# Core.net
KiCad netlist of a schematic drawn in Altium Designer
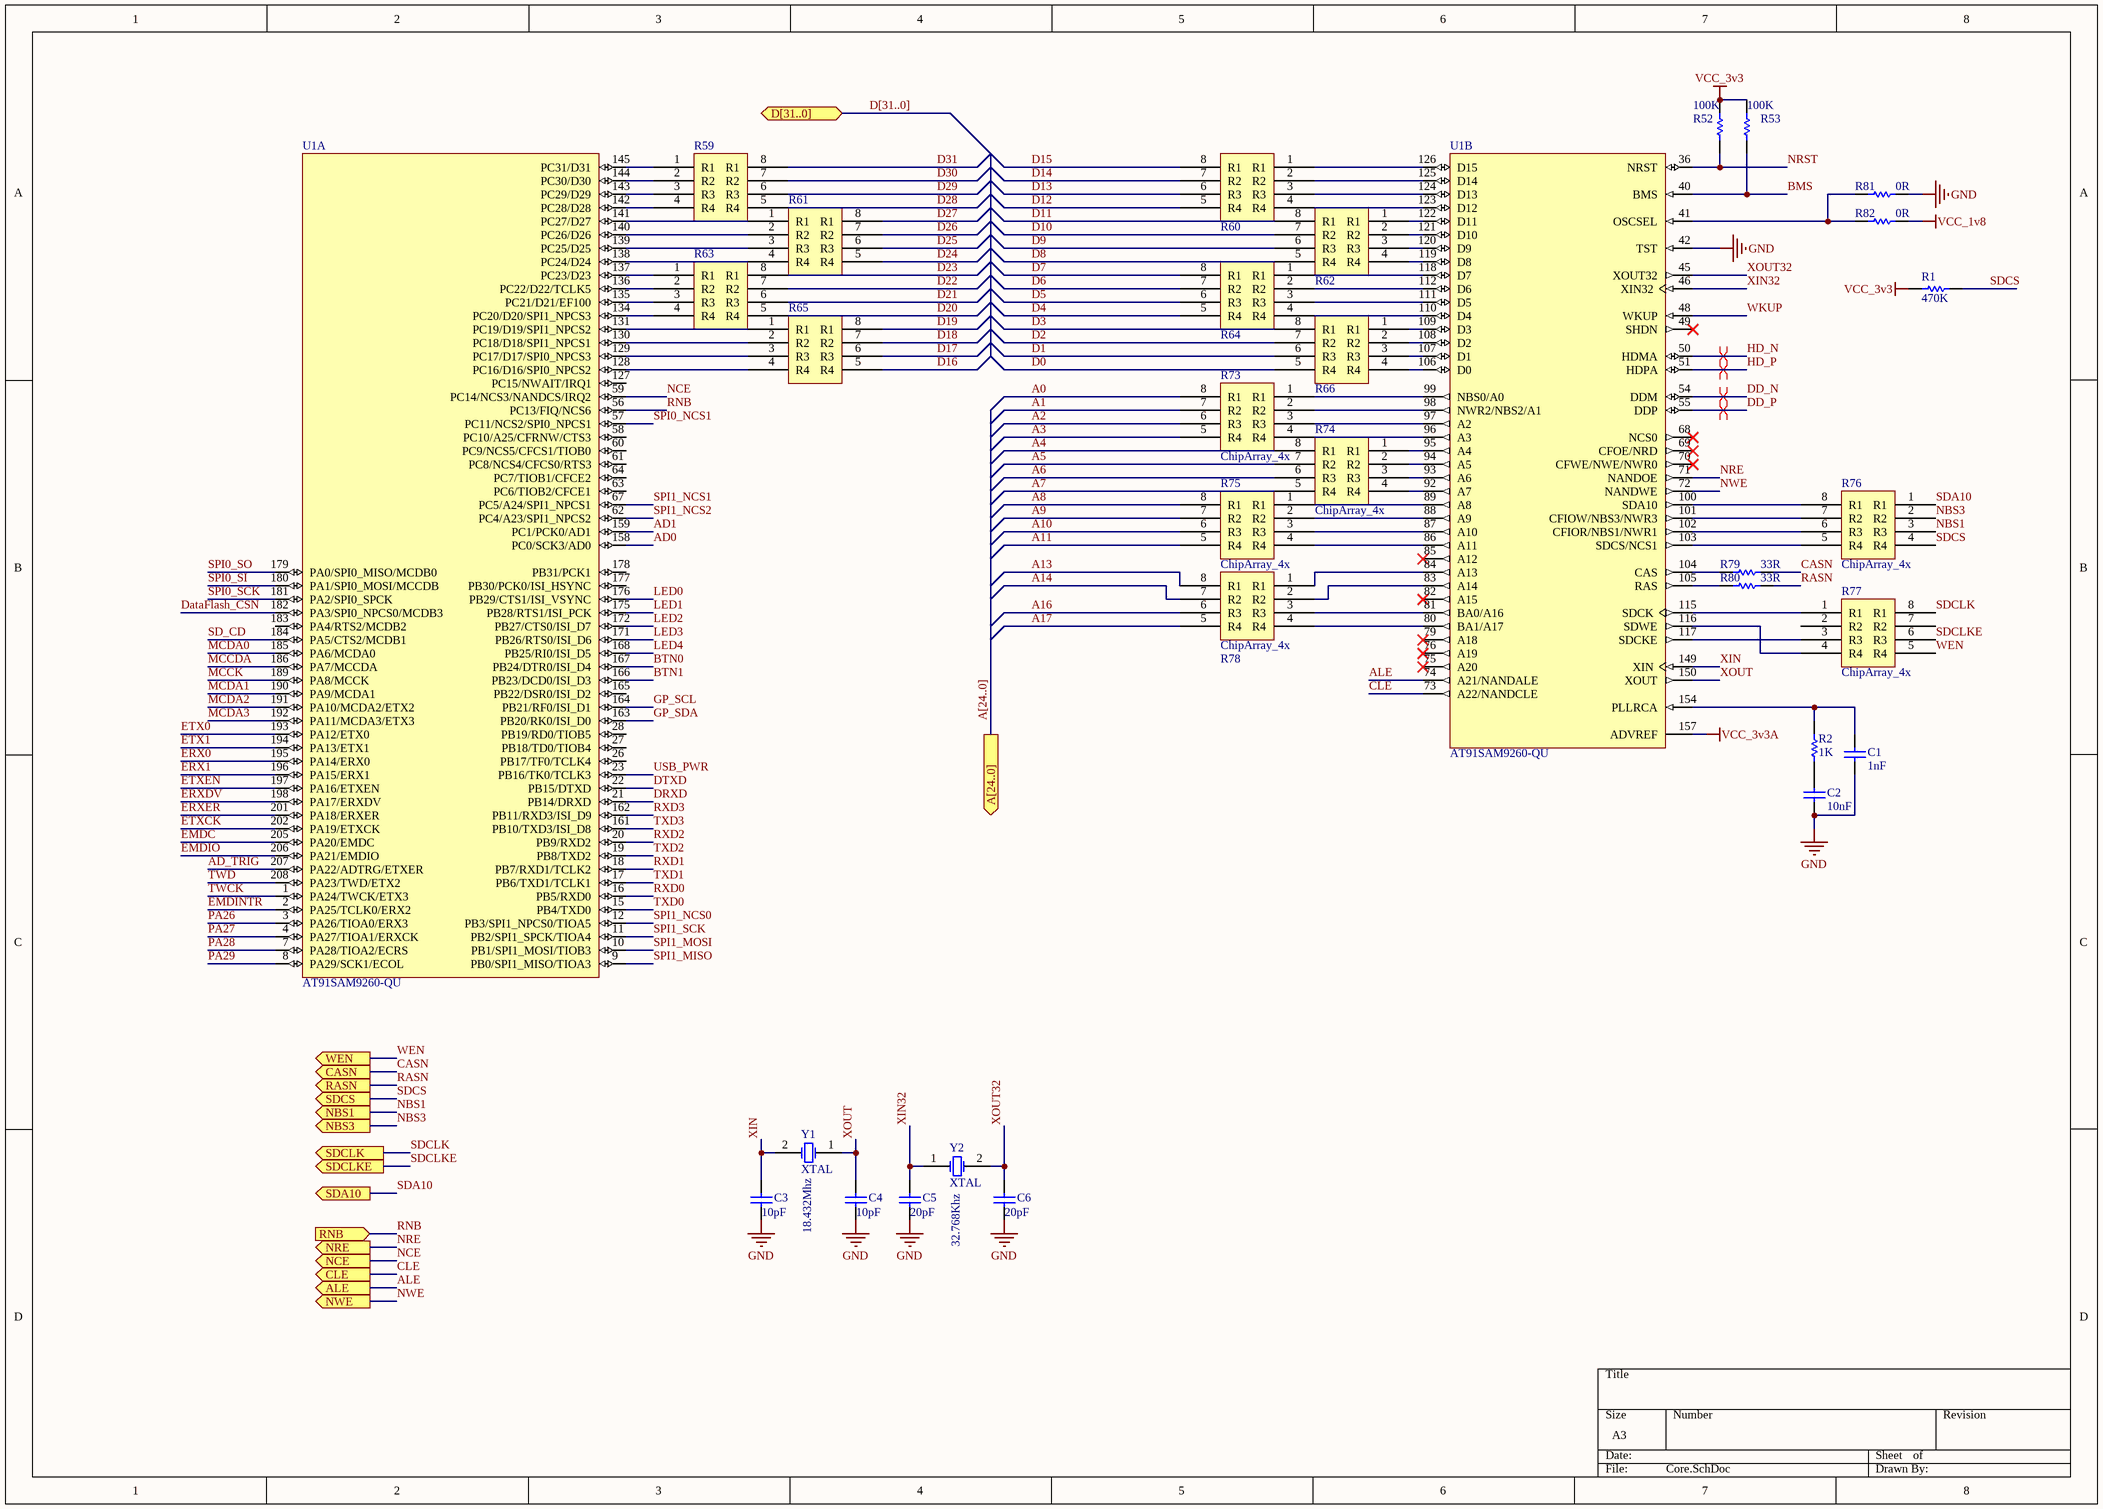
[diagram p0: Core.SchDoc]

(export (version "E")
  (design (tool "Eeschema 10.0.6"))
  (components
    (comp (ref "C1")
      (value "1nF")
      (footprint "C0805")
      (description "Capacitor")
      (fields (field (name "Comment") "Cap") (field (name "PUBLISHER") "Altium Limited"))
      (libsource (lib "Miscellaneous Devices") (part "Cap"))
    )
    (comp (ref "C2")
      (value "10nF")
      (footprint "C0805")
      (description "Capacitor")
      (fields (field (name "Comment") "Cap") (field (name "PUBLISHER") "Altium Limited"))
      (libsource (lib "Miscellaneous Devices") (part "Cap"))
    )
    (comp (ref "C3")
      (value "10pF")
      (footprint "C0805")
      (description "Capacitor")
      (fields (field (name "Comment") "Cap") (field (name "PUBLISHER") "Altium Limited"))
      (libsource (lib "Miscellaneous Devices") (part "Cap"))
    )
    (comp (ref "C4")
      (value "10pF")
      (footprint "C0805")
      (description "Capacitor")
      (fields (field (name "Comment") "Cap") (field (name "PUBLISHER") "Altium Limited"))
      (libsource (lib "Miscellaneous Devices") (part "Cap"))
    )
    (comp (ref "C5")
      (value "20pF")
      (footprint "0603PKG")
      (description "Capacitor")
      (fields (field (name "Comment") "Cap") (field (name "PUBLISHER") "Altium Limited"))
      (libsource (lib "Miscellaneous Devices") (part "Cap"))
    )
    (comp (ref "C6")
      (value "20pF")
      (footprint "0603PKG")
      (description "Capacitor")
      (fields (field (name "Comment") "Cap") (field (name "PUBLISHER") "Altium Limited"))
      (libsource (lib "Miscellaneous Devices") (part "Cap"))
    )
    (comp (ref "R1")
      (value "470K")
      (footprint "C0805")
      (description "Semiconductor Resistor")
      (fields (field (name "Comment") "Res Semi") (field (name "PUBLISHER") "Altium Limited"))
      (libsource (lib "Miscellaneous Devices") (part "Res Semi"))
    )
    (comp (ref "R2")
      (value "1K")
      (footprint "C0805")
      (description "Semiconductor Resistor")
      (fields (field (name "Comment") "Res Semi") (field (name "PUBLISHER") "Altium Limited"))
      (libsource (lib "Miscellaneous Devices") (part "Res Semi"))
    )
    (comp (ref "R52")
      (value "100K")
      (footprint "C0805")
      (description "Resistor")
      (fields (field (name "Comment") "Res1") (field (name "PUBLISHER") "Altium Limited"))
      (libsource (lib "Miscellaneous Devices") (part "Res1"))
    )
    (comp (ref "R53")
      (value "100K")
      (footprint "C0805")
      (description "Resistor")
      (fields (field (name "Comment") "Res1") (field (name "PUBLISHER") "Altium Limited"))
      (libsource (lib "Miscellaneous Devices") (part "Res1"))
    )
    (comp (ref "R59")
      (value "ChipArray_4x")
      (footprint "CAC-50P205X105-8M")
      (libsource (lib "") (part "ChipArray_4x_1"))
    )
    (comp (ref "R60")
      (value "ChipArray_4x")
      (footprint "CAC-50P205X105-8M")
      (libsource (lib "Connector_IntLib") (part "ChipArray_4x"))
    )
    (comp (ref "R61")
      (value "ChipArray_4x")
      (footprint "CAC-50P205X105-8M")
      (libsource (lib "") (part "ChipArray_4x_1"))
    )
    (comp (ref "R62")
      (value "ChipArray_4x")
      (footprint "CAC-50P205X105-8M")
      (libsource (lib "Connector_IntLib") (part "ChipArray_4x"))
    )
    (comp (ref "R63")
      (value "ChipArray_4x")
      (footprint "CAC-50P205X105-8M")
      (libsource (lib "") (part "ChipArray_4x_1"))
    )
    (comp (ref "R64")
      (value "ChipArray_4x")
      (footprint "CAC-50P205X105-8M")
      (libsource (lib "Connector_IntLib") (part "ChipArray_4x"))
    )
    (comp (ref "R65")
      (value "ChipArray_4x")
      (footprint "CAC-50P205X105-8M")
      (libsource (lib "") (part "ChipArray_4x_1"))
    )
    (comp (ref "R66")
      (value "ChipArray_4x")
      (footprint "CAC-50P205X105-8M")
      (libsource (lib "Connector_IntLib") (part "ChipArray_4x"))
    )
    (comp (ref "R73")
      (value "ChipArray_4x")
      (footprint "CAC-50P205X105-8M")
      (libsource (lib "Connector_IntLib") (part "ChipArray_4x"))
    )
    (comp (ref "R74")
      (value "ChipArray_4x")
      (footprint "CAC-50P205X105-8M")
      (libsource (lib "Connector_IntLib") (part "ChipArray_4x"))
    )
    (comp (ref "R75")
      (value "ChipArray_4x")
      (footprint "CAC-50P205X105-8M")
      (libsource (lib "Connector_IntLib") (part "ChipArray_4x"))
    )
    (comp (ref "R76")
      (value "ChipArray_4x")
      (footprint "CAC-50P205X105-8M")
      (libsource (lib "Connector_IntLib") (part "ChipArray_4x"))
    )
    (comp (ref "R77")
      (value "ChipArray_4x")
      (footprint "CAC-50P205X105-8M")
      (libsource (lib "") (part "ChipArray_4x_1"))
    )
    (comp (ref "R78")
      (value "ChipArray_4x")
      (footprint "CAC-50P205X105-8M")
      (libsource (lib "Connector_IntLib") (part "ChipArray_4x"))
    )
    (comp (ref "R79")
      (value "33R")
      (footprint "C0805")
      (description "Semiconductor Resistor")
      (fields (field (name "Comment") "Res Semi") (field (name "PUBLISHER") "Altium Limited"))
      (libsource (lib "Miscellaneous Devices") (part "Res Semi"))
    )
    (comp (ref "R80")
      (value "33R")
      (footprint "C0805")
      (description "Semiconductor Resistor")
      (fields (field (name "Comment") "Res Semi") (field (name "PUBLISHER") "Altium Limited"))
      (libsource (lib "Miscellaneous Devices") (part "Res Semi"))
    )
    (comp (ref "R81")
      (value "0R")
      (footprint "0603PKG")
      (description "Semiconductor Resistor")
      (fields (field (name "Comment") "Res Semi") (field (name "PUBLISHER") "Altium Limited"))
      (libsource (lib "Miscellaneous Devices") (part "Res Semi"))
    )
    (comp (ref "R82")
      (value "0R")
      (footprint "0603PKG")
      (description "Semiconductor Resistor")
      (fields (field (name "Comment") "Res Semi") (field (name "PUBLISHER") "Altium Limited"))
      (libsource (lib "Miscellaneous Devices") (part "Res Semi"))
    )
    (comp (ref "U1")
      (value "AT91SAM9260-QU")
      (footprint "SQFP50P3122X3122X245-208N")
      (libsource (lib "") (part "AT91SAM9260-QU_1"))
    )
    (comp (ref "Y1")
      (value "XTAL")
      (footprint "SMD_Crystal")
      (description "Crystal Oscillator")
      (fields (field (name "ALTIUM_VALUE") "18.432Mhz") (field (name "PUBLISHER") "Altium Limited"))
      (libsource (lib "Miscellaneous Devices") (part "XTAL"))
    )
    (comp (ref "Y2")
      (value "XTAL")
      (footprint "R38")
      (description "Crystal Oscillator")
      (fields (field (name "ALTIUM_VALUE") "32.768Khz") (field (name "PUBLISHER") "Altium Limited"))
      (libsource (lib "Miscellaneous Devices") (part "XTAL"))
    )
  )
  (nets
    (net (code "10") (name "/A0") (class "Default")
      (node (ref "R73") (pin "8") (pinfunction "R1_8") (pintype "passive"))
    )
    (net (code "11") (name "/A1") (class "Default")
      (node (ref "R73") (pin "7") (pinfunction "R2_7") (pintype "passive"))
    )
    (net (code "12") (name "/A2") (class "Default")
      (node (ref "R73") (pin "6") (pinfunction "R3_6") (pintype "passive"))
    )
    (net (code "13") (name "/A3") (class "Default")
      (node (ref "R73") (pin "5") (pinfunction "R4_5") (pintype "passive"))
    )
    (net (code "14") (name "/A4") (class "Default")
      (node (ref "R74") (pin "8") (pinfunction "R1_8") (pintype "passive"))
    )
    (net (code "15") (name "/A5") (class "Default")
      (node (ref "R74") (pin "7") (pinfunction "R2_7") (pintype "passive"))
    )
    (net (code "16") (name "/A6") (class "Default")
      (node (ref "R74") (pin "6") (pinfunction "R3_6") (pintype "passive"))
    )
    (net (code "17") (name "/A7") (class "Default")
      (node (ref "R74") (pin "5") (pinfunction "R4_5") (pintype "passive"))
    )
    (net (code "18") (name "/A8") (class "Default")
      (node (ref "R75") (pin "8") (pinfunction "R1_8") (pintype "passive"))
    )
    (net (code "19") (name "/A9") (class "Default")
      (node (ref "R75") (pin "7") (pinfunction "R2_7") (pintype "passive"))
    )
    (net (code "20") (name "/A10") (class "Default")
      (node (ref "R75") (pin "6") (pinfunction "R3_6") (pintype "passive"))
    )
    (net (code "21") (name "/A11") (class "Default")
      (node (ref "R75") (pin "5") (pinfunction "R4_5") (pintype "passive"))
    )
    (net (code "22") (name "/A13") (class "Default")
      (node (ref "R78") (pin "8") (pinfunction "R1_8") (pintype "passive"))
    )
    (net (code "23") (name "/A14") (class "Default")
      (node (ref "R78") (pin "7") (pinfunction "R2_7") (pintype "passive"))
    )
    (net (code "24") (name "/A16") (class "Default")
      (node (ref "R78") (pin "6") (pinfunction "R3_6") (pintype "passive"))
    )
    (net (code "25") (name "/A17") (class "Default")
      (node (ref "R78") (pin "5") (pinfunction "R4_5") (pintype "passive"))
    )
    (net (code "26") (name "/AD0") (class "Default")
      (node (ref "U1") (pin "158") (pinfunction "PC0/SCK3/AD0_158") (pintype "bidirectional"))
    )
    (net (code "27") (name "/AD1") (class "Default")
      (node (ref "U1") (pin "159") (pinfunction "PC1/PCK0/AD1_159") (pintype "bidirectional"))
    )
    (net (code "28") (name "/AD_TRIG") (class "Default")
      (node (ref "U1") (pin "207") (pinfunction "PA22/ADTRG/ETXER_207") (pintype "bidirectional"))
    )
    (net (code "29") (name "/ALE") (class "Default")
      (node (ref "U1") (pin "74") (pinfunction "A21/NANDALE_74") (pintype "output"))
    )
    (net (code "31") (name "/BMS") (class "Default")
      (node (ref "R53") (pin "1") (pinfunction "1_1") (pintype "passive"))
      (node (ref "U1") (pin "40") (pinfunction "BMS_40") (pintype "input"))
    )
    (net (code "32") (name "/BTN0") (class "Default")
      (node (ref "U1") (pin "167") (pinfunction "PB24/DTR0/ISI_D4_167") (pintype "bidirectional"))
    )
    (net (code "33") (name "/BTN1") (class "Default")
      (node (ref "U1") (pin "166") (pinfunction "PB23/DCD0/ISI_D3_166") (pintype "bidirectional"))
    )
    (net (code "34") (name "/CASN") (class "Default")
      (node (ref "R79") (pin "2") (pinfunction "2_2") (pintype "passive"))
    )
    (net (code "35") (name "/CLE") (class "Default")
      (node (ref "U1") (pin "73") (pinfunction "A22/NANDCLE_73") (pintype "output"))
    )
    (net (code "36") (name "/D0") (class "Default")
      (node (ref "R66") (pin "5") (pinfunction "R4_5") (pintype "passive"))
    )
    (net (code "37") (name "/D1") (class "Default")
      (node (ref "R66") (pin "6") (pinfunction "R3_6") (pintype "passive"))
    )
    (net (code "38") (name "/D2") (class "Default")
      (node (ref "R66") (pin "7") (pinfunction "R2_7") (pintype "passive"))
    )
    (net (code "39") (name "/D3") (class "Default")
      (node (ref "R66") (pin "8") (pinfunction "R1_8") (pintype "passive"))
    )
    (net (code "40") (name "/D4") (class "Default")
      (node (ref "R64") (pin "5") (pinfunction "R4_5") (pintype "passive"))
    )
    (net (code "41") (name "/D5") (class "Default")
      (node (ref "R64") (pin "6") (pinfunction "R3_6") (pintype "passive"))
    )
    (net (code "42") (name "/D6") (class "Default")
      (node (ref "R64") (pin "7") (pinfunction "R2_7") (pintype "passive"))
    )
    (net (code "43") (name "/D7") (class "Default")
      (node (ref "R64") (pin "8") (pinfunction "R1_8") (pintype "passive"))
    )
    (net (code "44") (name "/D8") (class "Default")
      (node (ref "R62") (pin "5") (pinfunction "R4_5") (pintype "passive"))
    )
    (net (code "45") (name "/D9") (class "Default")
      (node (ref "R62") (pin "6") (pinfunction "R3_6") (pintype "passive"))
    )
    (net (code "46") (name "/D10") (class "Default")
      (node (ref "R62") (pin "7") (pinfunction "R2_7") (pintype "passive"))
    )
    (net (code "47") (name "/D11") (class "Default")
      (node (ref "R62") (pin "8") (pinfunction "R1_8") (pintype "passive"))
    )
    (net (code "48") (name "/D12") (class "Default")
      (node (ref "R60") (pin "5") (pinfunction "R4_5") (pintype "passive"))
    )
    (net (code "49") (name "/D13") (class "Default")
      (node (ref "R60") (pin "6") (pinfunction "R3_6") (pintype "passive"))
    )
    (net (code "50") (name "/D14") (class "Default")
      (node (ref "R60") (pin "7") (pinfunction "R2_7") (pintype "passive"))
    )
    (net (code "51") (name "/D15") (class "Default")
      (node (ref "R60") (pin "8") (pinfunction "R1_8") (pintype "passive"))
    )
    (net (code "52") (name "/D16") (class "Default")
      (node (ref "R65") (pin "5") (pinfunction "R4_5") (pintype "passive"))
    )
    (net (code "53") (name "/D17") (class "Default")
      (node (ref "R65") (pin "6") (pinfunction "R3_6") (pintype "passive"))
    )
    (net (code "54") (name "/D18") (class "Default")
      (node (ref "R65") (pin "7") (pinfunction "R2_7") (pintype "passive"))
    )
    (net (code "55") (name "/D19") (class "Default")
      (node (ref "R65") (pin "8") (pinfunction "R1_8") (pintype "passive"))
    )
    (net (code "56") (name "/D20") (class "Default")
      (node (ref "R63") (pin "5") (pinfunction "R4_5") (pintype "passive"))
    )
    (net (code "57") (name "/D21") (class "Default")
      (node (ref "R63") (pin "6") (pinfunction "R3_6") (pintype "passive"))
    )
    (net (code "58") (name "/D22") (class "Default")
      (node (ref "R63") (pin "7") (pinfunction "R2_7") (pintype "passive"))
    )
    (net (code "59") (name "/D23") (class "Default")
      (node (ref "R63") (pin "8") (pinfunction "R1_8") (pintype "passive"))
    )
    (net (code "60") (name "/D24") (class "Default")
      (node (ref "R61") (pin "5") (pinfunction "R4_5") (pintype "passive"))
    )
    (net (code "61") (name "/D25") (class "Default")
      (node (ref "R61") (pin "6") (pinfunction "R3_6") (pintype "passive"))
    )
    (net (code "62") (name "/D26") (class "Default")
      (node (ref "R61") (pin "7") (pinfunction "R2_7") (pintype "passive"))
    )
    (net (code "63") (name "/D27") (class "Default")
      (node (ref "R61") (pin "8") (pinfunction "R1_8") (pintype "passive"))
    )
    (net (code "64") (name "/D28") (class "Default")
      (node (ref "R59") (pin "5") (pinfunction "R4_5") (pintype "passive"))
    )
    (net (code "65") (name "/D29") (class "Default")
      (node (ref "R59") (pin "6") (pinfunction "R3_6") (pintype "passive"))
    )
    (net (code "66") (name "/D30") (class "Default")
      (node (ref "R59") (pin "7") (pinfunction "R2_7") (pintype "passive"))
    )
    (net (code "67") (name "/D31") (class "Default")
      (node (ref "R59") (pin "8") (pinfunction "R1_8") (pintype "passive"))
    )
    (net (code "68") (name "/DD_N") (class "Default")
      (node (ref "U1") (pin "54") (pinfunction "DDM_54") (pintype "bidirectional"))
    )
    (net (code "69") (name "/DD_P") (class "Default")
      (node (ref "U1") (pin "55") (pinfunction "DDP_55") (pintype "bidirectional"))
    )
    (net (code "70") (name "/DRXD") (class "Default")
      (node (ref "U1") (pin "21") (pinfunction "PB14/DRXD_21") (pintype "bidirectional"))
    )
    (net (code "71") (name "/DTXD") (class "Default")
      (node (ref "U1") (pin "22") (pinfunction "PB15/DTXD_22") (pintype "bidirectional"))
    )
    (net (code "73") (name "/DataFlash_CSN") (class "Default")
      (node (ref "U1") (pin "182") (pinfunction "PA3/SPI0_NPCS0/MCDB3_182") (pintype "bidirectional"))
    )
    (net (code "74") (name "/EMDC") (class "Default")
      (node (ref "U1") (pin "205") (pinfunction "PA20/EMDC_205") (pintype "bidirectional"))
    )
    (net (code "75") (name "/EMDINTR") (class "Default")
      (node (ref "U1") (pin "2") (pinfunction "PA25/TCLK0/ERX2_2") (pintype "bidirectional"))
    )
    (net (code "76") (name "/EMDIO") (class "Default")
      (node (ref "U1") (pin "206") (pinfunction "PA21/EMDIO_206") (pintype "bidirectional"))
    )
    (net (code "77") (name "/ERX0") (class "Default")
      (node (ref "U1") (pin "195") (pinfunction "PA14/ERX0_195") (pintype "bidirectional"))
    )
    (net (code "78") (name "/ERX1") (class "Default")
      (node (ref "U1") (pin "196") (pinfunction "PA15/ERX1_196") (pintype "bidirectional"))
    )
    (net (code "79") (name "/ERXDV") (class "Default")
      (node (ref "U1") (pin "198") (pinfunction "PA17/ERXDV_198") (pintype "bidirectional"))
    )
    (net (code "80") (name "/ERXER") (class "Default")
      (node (ref "U1") (pin "201") (pinfunction "PA18/ERXER_201") (pintype "bidirectional"))
    )
    (net (code "81") (name "/ETX0") (class "Default")
      (node (ref "U1") (pin "193") (pinfunction "PA12/ETX0_193") (pintype "bidirectional"))
    )
    (net (code "82") (name "/ETX1") (class "Default")
      (node (ref "U1") (pin "194") (pinfunction "PA13/ETX1_194") (pintype "bidirectional"))
    )
    (net (code "83") (name "/ETXCK") (class "Default")
      (node (ref "U1") (pin "202") (pinfunction "PA19/ETXCK_202") (pintype "bidirectional"))
    )
    (net (code "84") (name "/ETXEN") (class "Default")
      (node (ref "U1") (pin "197") (pinfunction "PA16/ETXEN_197") (pintype "bidirectional"))
    )
    (net (code "85") (name "/GP_SCL") (class "Default")
      (node (ref "U1") (pin "164") (pinfunction "PB21/RF0/ISI_D1_164") (pintype "bidirectional"))
    )
    (net (code "86") (name "/GP_SDA") (class "Default")
      (node (ref "U1") (pin "163") (pinfunction "PB20/RK0/ISI_D0_163") (pintype "bidirectional"))
    )
    (net (code "87") (name "/HD_N") (class "Default")
      (node (ref "U1") (pin "50") (pinfunction "HDMA_50") (pintype "bidirectional"))
    )
    (net (code "88") (name "/HD_P") (class "Default")
      (node (ref "U1") (pin "51") (pinfunction "HDPA_51") (pintype "bidirectional"))
    )
    (net (code "89") (name "/LED0") (class "Default")
      (node (ref "U1") (pin "176") (pinfunction "PB29/CTS1/ISI_VSYNC_176") (pintype "bidirectional"))
    )
    (net (code "90") (name "/LED1") (class "Default")
      (node (ref "U1") (pin "175") (pinfunction "PB28/RTS1/ISI_PCK_175") (pintype "bidirectional"))
    )
    (net (code "91") (name "/LED2") (class "Default")
      (node (ref "U1") (pin "172") (pinfunction "PB27/CTS0/ISI_D7_172") (pintype "bidirectional"))
    )
    (net (code "92") (name "/LED3") (class "Default")
      (node (ref "U1") (pin "171") (pinfunction "PB26/RTS0/ISI_D6_171") (pintype "bidirectional"))
    )
    (net (code "93") (name "/LED4") (class "Default")
      (node (ref "U1") (pin "168") (pinfunction "PB25/RI0/ISI_D5_168") (pintype "bidirectional"))
    )
    (net (code "94") (name "/MCCDA") (class "Default")
      (node (ref "U1") (pin "186") (pinfunction "PA7/MCCDA_186") (pintype "bidirectional"))
    )
    (net (code "95") (name "/MCCK") (class "Default")
      (node (ref "U1") (pin "189") (pinfunction "PA8/MCCK_189") (pintype "bidirectional"))
    )
    (net (code "96") (name "/MCDA0") (class "Default")
      (node (ref "U1") (pin "185") (pinfunction "PA6/MCDA0_185") (pintype "bidirectional"))
    )
    (net (code "97") (name "/MCDA1") (class "Default")
      (node (ref "U1") (pin "190") (pinfunction "PA9/MCDA1_190") (pintype "bidirectional"))
    )
    (net (code "98") (name "/MCDA2") (class "Default")
      (node (ref "U1") (pin "191") (pinfunction "PA10/MCDA2/ETX2_191") (pintype "bidirectional"))
    )
    (net (code "99") (name "/MCDA3") (class "Default")
      (node (ref "U1") (pin "192") (pinfunction "PA11/MCDA3/ETX3_192") (pintype "bidirectional"))
    )
    (net (code "100") (name "/NBS1") (class "Default")
      (node (ref "R76") (pin "3") (pinfunction "R3_3") (pintype "passive"))
    )
    (net (code "101") (name "/NBS3") (class "Default")
      (node (ref "R76") (pin "2") (pinfunction "R2_2") (pintype "passive"))
    )
    (net (code "102") (name "/NCE") (class "Default")
      (node (ref "U1") (pin "59") (pinfunction "PC14/NCS3/NANDCS/IRQ2_59") (pintype "bidirectional"))
    )
    (net (code "103") (name "/NRE") (class "Default")
      (node (ref "U1") (pin "71") (pinfunction "NANDOE_71") (pintype "output"))
    )
    (net (code "104") (name "/NRST") (class "Default")
      (node (ref "R52") (pin "1") (pinfunction "1_1") (pintype "passive"))
      (node (ref "U1") (pin "36") (pinfunction "NRST_36") (pintype "bidirectional"))
    )
    (net (code "105") (name "/NWE") (class "Default")
      (node (ref "U1") (pin "72") (pinfunction "NANDWE_72") (pintype "output"))
    )
    (net (code "106") (name "/PA26") (class "Default")
      (node (ref "U1") (pin "3") (pinfunction "PA26/TIOA0/ERX3_3") (pintype "bidirectional"))
    )
    (net (code "107") (name "/PA27") (class "Default")
      (node (ref "U1") (pin "4") (pinfunction "PA27/TIOA1/ERXCK_4") (pintype "bidirectional"))
    )
    (net (code "108") (name "/PA28") (class "Default")
      (node (ref "U1") (pin "7") (pinfunction "PA28/TIOA2/ECRS_7") (pintype "bidirectional"))
    )
    (net (code "109") (name "/PA29") (class "Default")
      (node (ref "U1") (pin "8") (pinfunction "PA29/SCK1/ECOL_8") (pintype "bidirectional"))
    )
    (net (code "110") (name "/RASN") (class "Default")
      (node (ref "R80") (pin "2") (pinfunction "2_2") (pintype "passive"))
    )
    (net (code "111") (name "/RNB") (class "Default")
      (node (ref "U1") (pin "56") (pinfunction "PC13/FIQ/NCS6_56") (pintype "bidirectional"))
    )
    (net (code "112") (name "/RXD0") (class "Default")
      (node (ref "U1") (pin "16") (pinfunction "PB5/RXD0_16") (pintype "bidirectional"))
    )
    (net (code "113") (name "/RXD1") (class "Default")
      (node (ref "U1") (pin "18") (pinfunction "PB7/RXD1/TCLK2_18") (pintype "bidirectional"))
    )
    (net (code "114") (name "/RXD2") (class "Default")
      (node (ref "U1") (pin "20") (pinfunction "PB9/RXD2_20") (pintype "bidirectional"))
    )
    (net (code "115") (name "/RXD3") (class "Default")
      (node (ref "U1") (pin "162") (pinfunction "PB11/RXD3/ISI_D9_162") (pintype "bidirectional"))
    )
    (net (code "116") (name "/SDA10") (class "Default")
      (node (ref "R76") (pin "1") (pinfunction "R1_1") (pintype "passive"))
    )
    (net (code "117") (name "/SDCLK") (class "Default")
      (node (ref "R77") (pin "8") (pinfunction "R1_8") (pintype "passive"))
    )
    (net (code "118") (name "/SDCLKE") (class "Default")
      (node (ref "R77") (pin "6") (pinfunction "R3_6") (pintype "passive"))
    )
    (net (code "119") (name "/SDCS") (class "Default")
      (node (ref "R1") (pin "2") (pinfunction "2_2") (pintype "passive"))
      (node (ref "R76") (pin "4") (pinfunction "R4_4") (pintype "passive"))
    )
    (net (code "120") (name "/SD_CD") (class "Default")
      (node (ref "U1") (pin "184") (pinfunction "PA5/CTS2/MCDB1_184") (pintype "bidirectional"))
    )
    (net (code "121") (name "/SPI0_NCS1") (class "Default")
      (node (ref "U1") (pin "57") (pinfunction "PC11/NCS2/SPI0_NPCS1_57") (pintype "bidirectional"))
    )
    (net (code "122") (name "/SPI0_SCK") (class "Default")
      (node (ref "U1") (pin "181") (pinfunction "PA2/SPI0_SPCK_181") (pintype "bidirectional"))
    )
    (net (code "123") (name "/SPI0_SI") (class "Default")
      (node (ref "U1") (pin "180") (pinfunction "PA1/SPI0_MOSI/MCCDB_180") (pintype "bidirectional"))
    )
    (net (code "124") (name "/SPI0_SO") (class "Default")
      (node (ref "U1") (pin "179") (pinfunction "PA0/SPI0_MISO/MCDB0_179") (pintype "bidirectional"))
    )
    (net (code "125") (name "/SPI1_MISO") (class "Default")
      (node (ref "U1") (pin "9") (pinfunction "PB0/SPI1_MISO/TIOA3_9") (pintype "bidirectional"))
    )
    (net (code "126") (name "/SPI1_MOSI") (class "Default")
      (node (ref "U1") (pin "10") (pinfunction "PB1/SPI1_MOSI/TIOB3_10") (pintype "bidirectional"))
    )
    (net (code "127") (name "/SPI1_NCS0") (class "Default")
      (node (ref "U1") (pin "12") (pinfunction "PB3/SPI1_NPCS0/TIOA5_12") (pintype "bidirectional"))
    )
    (net (code "128") (name "/SPI1_NCS1") (class "Default")
      (node (ref "U1") (pin "67") (pinfunction "PC5/A24/SPI1_NPCS1_67") (pintype "bidirectional"))
    )
    (net (code "129") (name "/SPI1_NCS2") (class "Default")
      (node (ref "U1") (pin "62") (pinfunction "PC4/A23/SPI1_NPCS2_62") (pintype "bidirectional"))
    )
    (net (code "130") (name "/SPI1_SCK") (class "Default")
      (node (ref "U1") (pin "11") (pinfunction "PB2/SPI1_SPCK/TIOA4_11") (pintype "bidirectional"))
    )
    (net (code "131") (name "/TWCK") (class "Default")
      (node (ref "U1") (pin "1") (pinfunction "PA24/TWCK/ETX3_1") (pintype "bidirectional"))
    )
    (net (code "132") (name "/TWD") (class "Default")
      (node (ref "U1") (pin "208") (pinfunction "PA23/TWD/ETX2_208") (pintype "bidirectional"))
    )
    (net (code "133") (name "/TXD0") (class "Default")
      (node (ref "U1") (pin "15") (pinfunction "PB4/TXD0_15") (pintype "bidirectional"))
    )
    (net (code "134") (name "/TXD1") (class "Default")
      (node (ref "U1") (pin "17") (pinfunction "PB6/TXD1/TCLK1_17") (pintype "bidirectional"))
    )
    (net (code "135") (name "/TXD2") (class "Default")
      (node (ref "U1") (pin "19") (pinfunction "PB8/TXD2_19") (pintype "bidirectional"))
    )
    (net (code "136") (name "/TXD3") (class "Default")
      (node (ref "U1") (pin "161") (pinfunction "PB10/TXD3/ISI_D8_161") (pintype "bidirectional"))
    )
    (net (code "137") (name "/USB_PWR") (class "Default")
      (node (ref "U1") (pin "23") (pinfunction "PB16/TK0/TCLK3_23") (pintype "bidirectional"))
    )
    (net (code "138") (name "/WEN") (class "Default")
      (node (ref "R77") (pin "5") (pinfunction "R4_5") (pintype "passive"))
    )
    (net (code "139") (name "/WKUP") (class "Default")
      (node (ref "U1") (pin "48") (pinfunction "WKUP_48") (pintype "input"))
    )
    (net (code "140") (name "/XIN") (class "Default")
      (node (ref "C3") (pin "2") (pinfunction "2_2") (pintype "passive"))
      (node (ref "U1") (pin "149") (pinfunction "XIN_149") (pintype "input"))
      (node (ref "Y1") (pin "2") (pinfunction "OSC2_2") (pintype "passive"))
    )
    (net (code "141") (name "/XIN32") (class "Default")
      (node (ref "C5") (pin "2") (pinfunction "2_2") (pintype "passive"))
      (node (ref "U1") (pin "46") (pinfunction "XIN32_46") (pintype "input"))
      (node (ref "Y2") (pin "1") (pinfunction "OSC1_1") (pintype "passive"))
    )
    (net (code "142") (name "/XOUT") (class "Default")
      (node (ref "C4") (pin "2") (pinfunction "2_2") (pintype "passive"))
      (node (ref "U1") (pin "150") (pinfunction "XOUT_150") (pintype "output"))
      (node (ref "Y1") (pin "1") (pinfunction "OSC1_1") (pintype "passive"))
    )
    (net (code "143") (name "/XOUT32") (class "Default")
      (node (ref "C6") (pin "2") (pinfunction "2_2") (pintype "passive"))
      (node (ref "U1") (pin "45") (pinfunction "XOUT32_45") (pintype "output"))
      (node (ref "Y2") (pin "2") (pinfunction "OSC2_2") (pintype "passive"))
    )
    (net (code "144") (name "GND") (class "Default")
      (node (ref "C1") (pin "2") (pinfunction "2_2") (pintype "passive"))
      (node (ref "C2") (pin "1") (pinfunction "1_1") (pintype "passive"))
      (node (ref "C3") (pin "1") (pinfunction "1_1") (pintype "passive"))
      (node (ref "C4") (pin "1") (pinfunction "1_1") (pintype "passive"))
      (node (ref "C5") (pin "1") (pinfunction "1_1") (pintype "passive"))
      (node (ref "C6") (pin "1") (pinfunction "1_1") (pintype "passive"))
      (node (ref "R81") (pin "2") (pinfunction "2_2") (pintype "passive"))
      (node (ref "U1") (pin "42") (pinfunction "TST_42") (pintype "input"))
    )
    (net (code "145") (name "Net-(C2-Pad2)") (class "Default")
      (node (ref "C2") (pin "2") (pinfunction "2_2") (pintype "passive"))
      (node (ref "R2") (pin "1") (pinfunction "1_1") (pintype "passive"))
    )
    (net (code "146") (name "Net-(U1A-PC16{slash}D16{slash}SPI0_NPCS2)") (class "Default")
      (node (ref "R65") (pin "4") (pinfunction "R4_4") (pintype "passive"))
      (node (ref "U1") (pin "128") (pinfunction "PC16/D16/SPI0_NPCS2_128") (pintype "bidirectional"))
    )
    (net (code "147") (name "Net-(U1A-PC17{slash}D17{slash}SPI0_NPCS3)") (class "Default")
      (node (ref "R65") (pin "3") (pinfunction "R3_3") (pintype "passive"))
      (node (ref "U1") (pin "129") (pinfunction "PC17/D17/SPI0_NPCS3_129") (pintype "bidirectional"))
    )
    (net (code "148") (name "Net-(U1A-PC18{slash}D18{slash}SPI1_NPCS1)") (class "Default")
      (node (ref "R65") (pin "2") (pinfunction "R2_2") (pintype "passive"))
      (node (ref "U1") (pin "130") (pinfunction "PC18/D18/SPI1_NPCS1_130") (pintype "bidirectional"))
    )
    (net (code "149") (name "Net-(U1A-PC19{slash}D19{slash}SPI1_NPCS2)") (class "Default")
      (node (ref "R65") (pin "1") (pinfunction "R1_1") (pintype "passive"))
      (node (ref "U1") (pin "131") (pinfunction "PC19/D19/SPI1_NPCS2_131") (pintype "bidirectional"))
    )
    (net (code "150") (name "Net-(U1A-PC20{slash}D20{slash}SPI1_NPCS3)") (class "Default")
      (node (ref "R63") (pin "4") (pinfunction "R4_4") (pintype "passive"))
      (node (ref "U1") (pin "134") (pinfunction "PC20/D20/SPI1_NPCS3_134") (pintype "bidirectional"))
    )
    (net (code "151") (name "Net-(U1A-PC21{slash}D21{slash}EF100)") (class "Default")
      (node (ref "R63") (pin "3") (pinfunction "R3_3") (pintype "passive"))
      (node (ref "U1") (pin "135") (pinfunction "PC21/D21/EF100_135") (pintype "bidirectional"))
    )
    (net (code "152") (name "Net-(U1A-PC22{slash}D22{slash}TCLK5)") (class "Default")
      (node (ref "R63") (pin "2") (pinfunction "R2_2") (pintype "passive"))
      (node (ref "U1") (pin "136") (pinfunction "PC22/D22/TCLK5_136") (pintype "bidirectional"))
    )
    (net (code "153") (name "Net-(U1A-PC23{slash}D23)") (class "Default")
      (node (ref "R63") (pin "1") (pinfunction "R1_1") (pintype "passive"))
      (node (ref "U1") (pin "137") (pinfunction "PC23/D23_137") (pintype "bidirectional"))
    )
    (net (code "154") (name "Net-(U1A-PC24{slash}D24)") (class "Default")
      (node (ref "R61") (pin "4") (pinfunction "R4_4") (pintype "passive"))
      (node (ref "U1") (pin "138") (pinfunction "PC24/D24_138") (pintype "bidirectional"))
    )
    (net (code "155") (name "Net-(U1A-PC25{slash}D25)") (class "Default")
      (node (ref "R61") (pin "3") (pinfunction "R3_3") (pintype "passive"))
      (node (ref "U1") (pin "139") (pinfunction "PC25/D25_139") (pintype "bidirectional"))
    )
    (net (code "156") (name "Net-(U1A-PC26{slash}D26)") (class "Default")
      (node (ref "R61") (pin "2") (pinfunction "R2_2") (pintype "passive"))
      (node (ref "U1") (pin "140") (pinfunction "PC26/D26_140") (pintype "bidirectional"))
    )
    (net (code "157") (name "Net-(U1A-PC27{slash}D27)") (class "Default")
      (node (ref "R61") (pin "1") (pinfunction "R1_1") (pintype "passive"))
      (node (ref "U1") (pin "141") (pinfunction "PC27/D27_141") (pintype "bidirectional"))
    )
    (net (code "158") (name "Net-(U1A-PC28{slash}D28)") (class "Default")
      (node (ref "R59") (pin "4") (pinfunction "R4_4") (pintype "passive"))
      (node (ref "U1") (pin "142") (pinfunction "PC28/D28_142") (pintype "bidirectional"))
    )
    (net (code "159") (name "Net-(U1A-PC29{slash}D29)") (class "Default")
      (node (ref "R59") (pin "3") (pinfunction "R3_3") (pintype "passive"))
      (node (ref "U1") (pin "143") (pinfunction "PC29/D29_143") (pintype "bidirectional"))
    )
    (net (code "160") (name "Net-(U1A-PC30{slash}D30)") (class "Default")
      (node (ref "R59") (pin "2") (pinfunction "R2_2") (pintype "passive"))
      (node (ref "U1") (pin "144") (pinfunction "PC30/D30_144") (pintype "bidirectional"))
    )
    (net (code "161") (name "Net-(U1A-PC31{slash}D31)") (class "Default")
      (node (ref "R59") (pin "1") (pinfunction "R1_1") (pintype "passive"))
      (node (ref "U1") (pin "145") (pinfunction "PC31/D31_145") (pintype "bidirectional"))
    )
    (net (code "162") (name "Net-(U1B-A2)") (class "Default")
      (node (ref "R73") (pin "3") (pinfunction "R3_3") (pintype "passive"))
      (node (ref "U1") (pin "97") (pinfunction "A2_97") (pintype "output"))
    )
    (net (code "163") (name "Net-(U1B-A3)") (class "Default")
      (node (ref "R73") (pin "4") (pinfunction "R4_4") (pintype "passive"))
      (node (ref "U1") (pin "96") (pinfunction "A3_96") (pintype "output"))
    )
    (net (code "164") (name "Net-(U1B-A4)") (class "Default")
      (node (ref "R74") (pin "1") (pinfunction "R1_1") (pintype "passive"))
      (node (ref "U1") (pin "95") (pinfunction "A4_95") (pintype "output"))
    )
    (net (code "165") (name "Net-(U1B-A5)") (class "Default")
      (node (ref "R74") (pin "2") (pinfunction "R2_2") (pintype "passive"))
      (node (ref "U1") (pin "94") (pinfunction "A5_94") (pintype "output"))
    )
    (net (code "166") (name "Net-(U1B-A6)") (class "Default")
      (node (ref "R74") (pin "3") (pinfunction "R3_3") (pintype "passive"))
      (node (ref "U1") (pin "93") (pinfunction "A6_93") (pintype "output"))
    )
    (net (code "167") (name "Net-(U1B-A7)") (class "Default")
      (node (ref "R74") (pin "4") (pinfunction "R4_4") (pintype "passive"))
      (node (ref "U1") (pin "92") (pinfunction "A7_92") (pintype "output"))
    )
    (net (code "168") (name "Net-(U1B-A8)") (class "Default")
      (node (ref "R75") (pin "1") (pinfunction "R1_1") (pintype "passive"))
      (node (ref "U1") (pin "89") (pinfunction "A8_89") (pintype "output"))
    )
    (net (code "169") (name "Net-(U1B-A9)") (class "Default")
      (node (ref "R75") (pin "2") (pinfunction "R2_2") (pintype "passive"))
      (node (ref "U1") (pin "88") (pinfunction "A9_88") (pintype "output"))
    )
    (net (code "170") (name "Net-(U1B-A10)") (class "Default")
      (node (ref "R75") (pin "3") (pinfunction "R3_3") (pintype "passive"))
      (node (ref "U1") (pin "87") (pinfunction "A10_87") (pintype "output"))
    )
    (net (code "171") (name "Net-(U1B-A11)") (class "Default")
      (node (ref "R75") (pin "4") (pinfunction "R4_4") (pintype "passive"))
      (node (ref "U1") (pin "86") (pinfunction "A11_86") (pintype "output"))
    )
    (net (code "172") (name "Net-(U1B-A13)") (class "Default")
      (node (ref "R78") (pin "1") (pinfunction "R1_1") (pintype "passive"))
      (node (ref "U1") (pin "84") (pinfunction "A13_84") (pintype "output"))
    )
    (net (code "173") (name "Net-(U1B-A14)") (class "Default")
      (node (ref "R78") (pin "2") (pinfunction "R2_2") (pintype "passive"))
      (node (ref "U1") (pin "83") (pinfunction "A14_83") (pintype "output"))
    )
    (net (code "174") (name "Net-(U1B-BA0{slash}A16)") (class "Default")
      (node (ref "R78") (pin "3") (pinfunction "R3_3") (pintype "passive"))
      (node (ref "U1") (pin "81") (pinfunction "BA0/A16_81") (pintype "output"))
    )
    (net (code "175") (name "Net-(U1B-BA1{slash}A17)") (class "Default")
      (node (ref "R78") (pin "4") (pinfunction "R4_4") (pintype "passive"))
      (node (ref "U1") (pin "80") (pinfunction "BA1/A17_80") (pintype "output"))
    )
    (net (code "176") (name "Net-(U1B-CAS)") (class "Default")
      (node (ref "R79") (pin "1") (pinfunction "1_1") (pintype "passive"))
      (node (ref "U1") (pin "104") (pinfunction "CAS_104") (pintype "output"))
    )
    (net (code "177") (name "Net-(U1B-CFIOR{slash}NBS1{slash}NWR1)") (class "Default")
      (node (ref "R76") (pin "6") (pinfunction "R3_6") (pintype "passive"))
      (node (ref "U1") (pin "102") (pinfunction "CFIOR/NBS1/NWR1_102") (pintype "output"))
    )
    (net (code "178") (name "Net-(U1B-CFIOW{slash}NBS3{slash}NWR3)") (class "Default")
      (node (ref "R76") (pin "7") (pinfunction "R2_7") (pintype "passive"))
      (node (ref "U1") (pin "101") (pinfunction "CFIOW/NBS3/NWR3_101") (pintype "output"))
    )
    (net (code "179") (name "Net-(U1B-D0)") (class "Default")
      (node (ref "R66") (pin "4") (pinfunction "R4_4") (pintype "passive"))
      (node (ref "U1") (pin "106") (pinfunction "D0_106") (pintype "bidirectional"))
    )
    (net (code "180") (name "Net-(U1B-D1)") (class "Default")
      (node (ref "R66") (pin "3") (pinfunction "R3_3") (pintype "passive"))
      (node (ref "U1") (pin "107") (pinfunction "D1_107") (pintype "bidirectional"))
    )
    (net (code "181") (name "Net-(U1B-D2)") (class "Default")
      (node (ref "R66") (pin "2") (pinfunction "R2_2") (pintype "passive"))
      (node (ref "U1") (pin "108") (pinfunction "D2_108") (pintype "bidirectional"))
    )
    (net (code "182") (name "Net-(U1B-D3)") (class "Default")
      (node (ref "R66") (pin "1") (pinfunction "R1_1") (pintype "passive"))
      (node (ref "U1") (pin "109") (pinfunction "D3_109") (pintype "bidirectional"))
    )
    (net (code "183") (name "Net-(U1B-D4)") (class "Default")
      (node (ref "R64") (pin "4") (pinfunction "R4_4") (pintype "passive"))
      (node (ref "U1") (pin "110") (pinfunction "D4_110") (pintype "bidirectional"))
    )
    (net (code "184") (name "Net-(U1B-D5)") (class "Default")
      (node (ref "R64") (pin "3") (pinfunction "R3_3") (pintype "passive"))
      (node (ref "U1") (pin "111") (pinfunction "D5_111") (pintype "bidirectional"))
    )
    (net (code "185") (name "Net-(U1B-D6)") (class "Default")
      (node (ref "R64") (pin "2") (pinfunction "R2_2") (pintype "passive"))
      (node (ref "U1") (pin "112") (pinfunction "D6_112") (pintype "bidirectional"))
    )
    (net (code "186") (name "Net-(U1B-D7)") (class "Default")
      (node (ref "R64") (pin "1") (pinfunction "R1_1") (pintype "passive"))
      (node (ref "U1") (pin "118") (pinfunction "D7_118") (pintype "bidirectional"))
    )
    (net (code "187") (name "Net-(U1B-D8)") (class "Default")
      (node (ref "R62") (pin "4") (pinfunction "R4_4") (pintype "passive"))
      (node (ref "U1") (pin "119") (pinfunction "D8_119") (pintype "bidirectional"))
    )
    (net (code "188") (name "Net-(U1B-D9)") (class "Default")
      (node (ref "R62") (pin "3") (pinfunction "R3_3") (pintype "passive"))
      (node (ref "U1") (pin "120") (pinfunction "D9_120") (pintype "bidirectional"))
    )
    (net (code "189") (name "Net-(U1B-D10)") (class "Default")
      (node (ref "R62") (pin "2") (pinfunction "R2_2") (pintype "passive"))
      (node (ref "U1") (pin "121") (pinfunction "D10_121") (pintype "bidirectional"))
    )
    (net (code "190") (name "Net-(U1B-D11)") (class "Default")
      (node (ref "R62") (pin "1") (pinfunction "R1_1") (pintype "passive"))
      (node (ref "U1") (pin "122") (pinfunction "D11_122") (pintype "bidirectional"))
    )
    (net (code "191") (name "Net-(U1B-D12)") (class "Default")
      (node (ref "R60") (pin "4") (pinfunction "R4_4") (pintype "passive"))
      (node (ref "U1") (pin "123") (pinfunction "D12_123") (pintype "bidirectional"))
    )
    (net (code "192") (name "Net-(U1B-D13)") (class "Default")
      (node (ref "R60") (pin "3") (pinfunction "R3_3") (pintype "passive"))
      (node (ref "U1") (pin "124") (pinfunction "D13_124") (pintype "bidirectional"))
    )
    (net (code "193") (name "Net-(U1B-D14)") (class "Default")
      (node (ref "R60") (pin "2") (pinfunction "R2_2") (pintype "passive"))
      (node (ref "U1") (pin "125") (pinfunction "D14_125") (pintype "bidirectional"))
    )
    (net (code "194") (name "Net-(U1B-D15)") (class "Default")
      (node (ref "R60") (pin "1") (pinfunction "R1_1") (pintype "passive"))
      (node (ref "U1") (pin "126") (pinfunction "D15_126") (pintype "bidirectional"))
    )
    (net (code "195") (name "Net-(U1B-NBS0{slash}A0)") (class "Default")
      (node (ref "R73") (pin "1") (pinfunction "R1_1") (pintype "passive"))
      (node (ref "U1") (pin "99") (pinfunction "NBS0/A0_99") (pintype "output"))
    )
    (net (code "196") (name "Net-(U1B-NWR2{slash}NBS2{slash}A1)") (class "Default")
      (node (ref "R73") (pin "2") (pinfunction "R2_2") (pintype "passive"))
      (node (ref "U1") (pin "98") (pinfunction "NWR2/NBS2/A1_98") (pintype "output"))
    )
    (net (code "197") (name "Net-(U1B-OSCSEL)") (class "Default")
      (node (ref "R81") (pin "1") (pinfunction "1_1") (pintype "passive"))
      (node (ref "R82") (pin "1") (pinfunction "1_1") (pintype "passive"))
      (node (ref "U1") (pin "41") (pinfunction "OSCSEL_41") (pintype "input"))
    )
    (net (code "198") (name "Net-(U1B-PLLRCA)") (class "Default")
      (node (ref "C1") (pin "1") (pinfunction "1_1") (pintype "passive"))
      (node (ref "R2") (pin "2") (pinfunction "2_2") (pintype "passive"))
      (node (ref "U1") (pin "154") (pinfunction "PLLRCA_154") (pintype "input"))
    )
    (net (code "199") (name "Net-(U1B-RAS)") (class "Default")
      (node (ref "R80") (pin "1") (pinfunction "1_1") (pintype "passive"))
      (node (ref "U1") (pin "105") (pinfunction "RAS_105") (pintype "output"))
    )
    (net (code "200") (name "Net-(U1B-SDA10)") (class "Default")
      (node (ref "R76") (pin "8") (pinfunction "R1_8") (pintype "passive"))
      (node (ref "U1") (pin "100") (pinfunction "SDA10_100") (pintype "output"))
    )
    (net (code "201") (name "Net-(U1B-SDCK)") (class "Default")
      (node (ref "R77") (pin "1") (pinfunction "R1_1") (pintype "passive"))
      (node (ref "U1") (pin "115") (pinfunction "SDCK_115") (pintype "output"))
    )
    (net (code "202") (name "Net-(U1B-SDCKE)") (class "Default")
      (node (ref "R77") (pin "3") (pinfunction "R3_3") (pintype "passive"))
      (node (ref "U1") (pin "117") (pinfunction "SDCKE_117") (pintype "output"))
    )
    (net (code "203") (name "Net-(U1B-SDCS{slash}NCS1)") (class "Default")
      (node (ref "R76") (pin "5") (pinfunction "R4_5") (pintype "passive"))
      (node (ref "U1") (pin "103") (pinfunction "SDCS/NCS1_103") (pintype "output"))
    )
    (net (code "204") (name "Net-(U1B-SDWE)") (class "Default")
      (node (ref "R77") (pin "4") (pinfunction "R4_4") (pintype "passive"))
      (node (ref "U1") (pin "116") (pinfunction "SDWE_116") (pintype "output"))
    )
    (net (code "205") (name "VCC_1v8") (class "Default")
      (node (ref "R82") (pin "2") (pinfunction "2_2") (pintype "passive"))
    )
    (net (code "206") (name "VCC_3v3") (class "Default")
      (node (ref "R1") (pin "1") (pinfunction "1_1") (pintype "passive"))
      (node (ref "R52") (pin "2") (pinfunction "2_2") (pintype "passive"))
      (node (ref "R53") (pin "2") (pinfunction "2_2") (pintype "passive"))
    )
    (net (code "207") (name "VCC_3v3A") (class "Default")
      (node (ref "U1") (pin "157") (pinfunction "ADVREF_157") (pintype "power_in"))
    )
    (net (code "208") (name "unconnected-(R77-R2-Pad2)") (class "Default")
      (node (ref "R77") (pin "2") (pinfunction "R2_2") (pintype "passive"))
    )
    (net (code "209") (name "unconnected-(R77-R2-Pad7)") (class "Default")
      (node (ref "R77") (pin "7") (pinfunction "R2_7") (pintype "passive"))
    )
    (net (code "210") (name "unconnected-(U1A-PA4{slash}RTS2{slash}MCDB2-Pad183)") (class "Default")
      (node (ref "U1") (pin "183") (pinfunction "PA4/RTS2/MCDB2_183") (pintype "bidirectional"))
    )
    (net (code "211") (name "unconnected-(U1A-PB17{slash}TF0{slash}TCLK4-Pad26)") (class "Default")
      (node (ref "U1") (pin "26") (pinfunction "PB17/TF0/TCLK4_26") (pintype "bidirectional"))
    )
    (net (code "212") (name "unconnected-(U1A-PB18{slash}TD0{slash}TIOB4-Pad27)") (class "Default")
      (node (ref "U1") (pin "27") (pinfunction "PB18/TD0/TIOB4_27") (pintype "bidirectional"))
    )
    (net (code "213") (name "unconnected-(U1A-PB19{slash}RD0{slash}TIOB5-Pad28)") (class "Default")
      (node (ref "U1") (pin "28") (pinfunction "PB19/RD0/TIOB5_28") (pintype "bidirectional"))
    )
    (net (code "214") (name "unconnected-(U1A-PB22{slash}DSR0{slash}ISI_D2-Pad165)") (class "Default")
      (node (ref "U1") (pin "165") (pinfunction "PB22/DSR0/ISI_D2_165") (pintype "bidirectional"))
    )
    (net (code "215") (name "unconnected-(U1A-PB30{slash}PCK0{slash}ISI_HSYNC-Pad177)") (class "Default")
      (node (ref "U1") (pin "177") (pinfunction "PB30/PCK0/ISI_HSYNC_177") (pintype "bidirectional"))
    )
    (net (code "216") (name "unconnected-(U1A-PB31{slash}PCK1-Pad178)") (class "Default")
      (node (ref "U1") (pin "178") (pinfunction "PB31/PCK1_178") (pintype "bidirectional"))
    )
    (net (code "217") (name "unconnected-(U1A-PC6{slash}TIOB2{slash}CFCE1-Pad63)") (class "Default")
      (node (ref "U1") (pin "63") (pinfunction "PC6/TIOB2/CFCE1_63") (pintype "bidirectional"))
    )
    (net (code "218") (name "unconnected-(U1A-PC7{slash}TIOB1{slash}CFCE2-Pad64)") (class "Default")
      (node (ref "U1") (pin "64") (pinfunction "PC7/TIOB1/CFCE2_64") (pintype "bidirectional"))
    )
    (net (code "219") (name "unconnected-(U1A-PC8{slash}NCS4{slash}CFCS0{slash}RTS3-Pad61)") (class "Default")
      (node (ref "U1") (pin "61") (pinfunction "PC8/NCS4/CFCS0/RTS3_61") (pintype "bidirectional"))
    )
    (net (code "220") (name "unconnected-(U1A-PC9{slash}NCS5{slash}CFCS1{slash}TIOB0-Pad60)") (class "Default")
      (node (ref "U1") (pin "60") (pinfunction "PC9/NCS5/CFCS1/TIOB0_60") (pintype "bidirectional"))
    )
    (net (code "221") (name "unconnected-(U1A-PC10{slash}A25{slash}CFRNW{slash}CTS3-Pad58)") (class "Default")
      (node (ref "U1") (pin "58") (pinfunction "PC10/A25/CFRNW/CTS3_58") (pintype "bidirectional"))
    )
    (net (code "222") (name "unconnected-(U1A-PC15{slash}NWAIT{slash}IRQ1-Pad127)") (class "Default")
      (node (ref "U1") (pin "127") (pinfunction "PC15/NWAIT/IRQ1_127") (pintype "bidirectional"))
    )
    (net (code "223") (name "unconnected-(U1B-A12-Pad85)") (class "Default")
      (node (ref "U1") (pin "85") (pinfunction "A12_85") (pintype "output+no_connect"))
    )
    (net (code "224") (name "unconnected-(U1B-A15-Pad82)") (class "Default")
      (node (ref "U1") (pin "82") (pinfunction "A15_82") (pintype "output+no_connect"))
    )
    (net (code "225") (name "unconnected-(U1B-A18-Pad79)") (class "Default")
      (node (ref "U1") (pin "79") (pinfunction "A18_79") (pintype "output+no_connect"))
    )
    (net (code "226") (name "unconnected-(U1B-A19-Pad76)") (class "Default")
      (node (ref "U1") (pin "76") (pinfunction "A19_76") (pintype "output+no_connect"))
    )
    (net (code "227") (name "unconnected-(U1B-A20-Pad75)") (class "Default")
      (node (ref "U1") (pin "75") (pinfunction "A20_75") (pintype "output+no_connect"))
    )
    (net (code "228") (name "unconnected-(U1B-CFOE{slash}NRD-Pad69)") (class "Default")
      (node (ref "U1") (pin "69") (pinfunction "CFOE/NRD_69") (pintype "output+no_connect"))
    )
    (net (code "229") (name "unconnected-(U1B-CFWE{slash}NWE{slash}NWR0-Pad70)") (class "Default")
      (node (ref "U1") (pin "70") (pinfunction "CFWE/NWE/NWR0_70") (pintype "output+no_connect"))
    )
    (net (code "230") (name "unconnected-(U1B-NCS0-Pad68)") (class "Default")
      (node (ref "U1") (pin "68") (pinfunction "NCS0_68") (pintype "output+no_connect"))
    )
    (net (code "231") (name "unconnected-(U1B-SHDN-Pad49)") (class "Default")
      (node (ref "U1") (pin "49") (pinfunction "SHDN_49") (pintype "output+no_connect"))
    )
  )
)
